# TwiddleStick.net
KiCad netlist of a schematic drawn in EAGLE
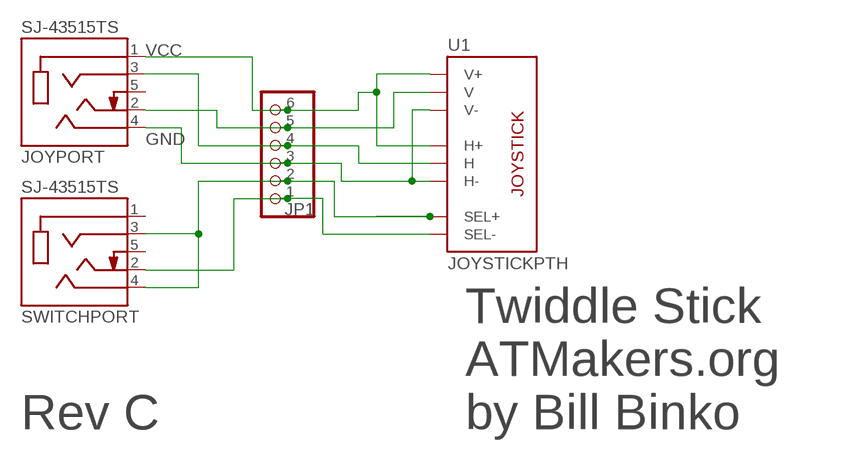
[diagram p0: schematic, sheet 1]

(export (version "E")
  (design (tool "Eeschema 10.0.6"))
  (components
    (comp (ref "JOYPORT")
      (value "SJ-43515TS")
      (footprint "eagle-import:CUI_SJ-43515TS")
      (fields (field (name "MF") "CUI Devices"))
      (libsource (lib "eagle-import") (part "SJ-43515TS"))
    )
    (comp (ref "JP1")
      (value "PINHD-1X6B")
      (footprint "eagle-import:1X06-BIG")
      (libsource (lib "eagle-import") (part "PINHD-1X6B"))
    )
    (comp (ref "SWITCHPORT")
      (value "SJ-43515TS")
      (footprint "eagle-import:CUI_SJ-43515TS")
      (fields (field (name "MF") "CUI Devices"))
      (libsource (lib "eagle-import") (part "SJ-43515TS"))
    )
    (comp (ref "U1")
      (value "JOYSTICKPTH")
      (footprint "eagle-import:JOYSTICK")
      (libsource (lib "eagle-import") (part "JOYSTICKPTH"))
    )
  )
  (nets
    (net (code "1") (name "/GND") (class "Default")
      (node (ref "JOYPORT") (pin "4") (pinfunction "RING2_4") (pintype "passive"))
      (node (ref "JP1") (pin "3") (pinfunction "3_3") (pintype "passive"))
      (node (ref "U1") (pin "H3") (pinfunction "H-_H3") (pintype "bidirectional"))
      (node (ref "U1") (pin "V3") (pinfunction "V-_V3") (pintype "bidirectional"))
    )
    (net (code "2") (name "/VCC") (class "Default")
      (node (ref "JOYPORT") (pin "1") (pinfunction "SLEEVE_1") (pintype "passive"))
      (node (ref "JP1") (pin "6") (pinfunction "6_6") (pintype "passive"))
      (node (ref "U1") (pin "H1") (pinfunction "H+_H1") (pintype "bidirectional"))
      (node (ref "U1") (pin "V1") (pinfunction "V+_V1") (pintype "bidirectional"))
    )
    (net (code "3") (name "Net-(JOYPORT-RING1)") (class "Default")
      (node (ref "JOYPORT") (pin "3") (pinfunction "RING1_3") (pintype "passive"))
      (node (ref "JP1") (pin "4") (pinfunction "4_4") (pintype "passive"))
      (node (ref "U1") (pin "H2") (pinfunction "H_H2") (pintype "bidirectional"))
    )
    (net (code "4") (name "Net-(JOYPORT-TIP)") (class "Default")
      (node (ref "JOYPORT") (pin "2") (pinfunction "TIP_2") (pintype "passive"))
      (node (ref "JP1") (pin "5") (pinfunction "5_5") (pintype "passive"))
      (node (ref "U1") (pin "V2") (pinfunction "V_V2") (pintype "bidirectional"))
    )
    (net (code "5") (name "Net-(SWITCHPORT-RING1)") (class "Default")
      (node (ref "JP1") (pin "2") (pinfunction "2_2") (pintype "passive"))
      (node (ref "SWITCHPORT") (pin "3") (pinfunction "RING1_3") (pintype "passive"))
      (node (ref "SWITCHPORT") (pin "4") (pinfunction "RING2_4") (pintype "passive"))
      (node (ref "U1") (pin "B1A") (pinfunction "SEL+_B1A") (pintype "bidirectional"))
    )
    (net (code "6") (name "Net-(SWITCHPORT-TIP)") (class "Default")
      (node (ref "JP1") (pin "1") (pinfunction "1_1") (pintype "passive"))
      (node (ref "SWITCHPORT") (pin "2") (pinfunction "TIP_2") (pintype "passive"))
      (node (ref "U1") (pin "B2A") (pinfunction "SEL-_B2A") (pintype "bidirectional"))
    )
    (net (code "7") (name "unconnected-(JOYPORT-TIP_SWITCH-Pad5)") (class "Default")
      (node (ref "JOYPORT") (pin "5") (pinfunction "TIP_SWITCH_5") (pintype "passive"))
    )
    (net (code "8") (name "unconnected-(SWITCHPORT-SLEEVE-Pad1)") (class "Default")
      (node (ref "SWITCHPORT") (pin "1") (pinfunction "SLEEVE_1") (pintype "passive"))
    )
    (net (code "9") (name "unconnected-(SWITCHPORT-TIP_SWITCH-Pad5)") (class "Default")
      (node (ref "SWITCHPORT") (pin "5") (pinfunction "TIP_SWITCH_5") (pintype "passive"))
    )
  )
)
